# Digital_Output_Board.net
KiCad netlist of a schematic drawn in EAGLE
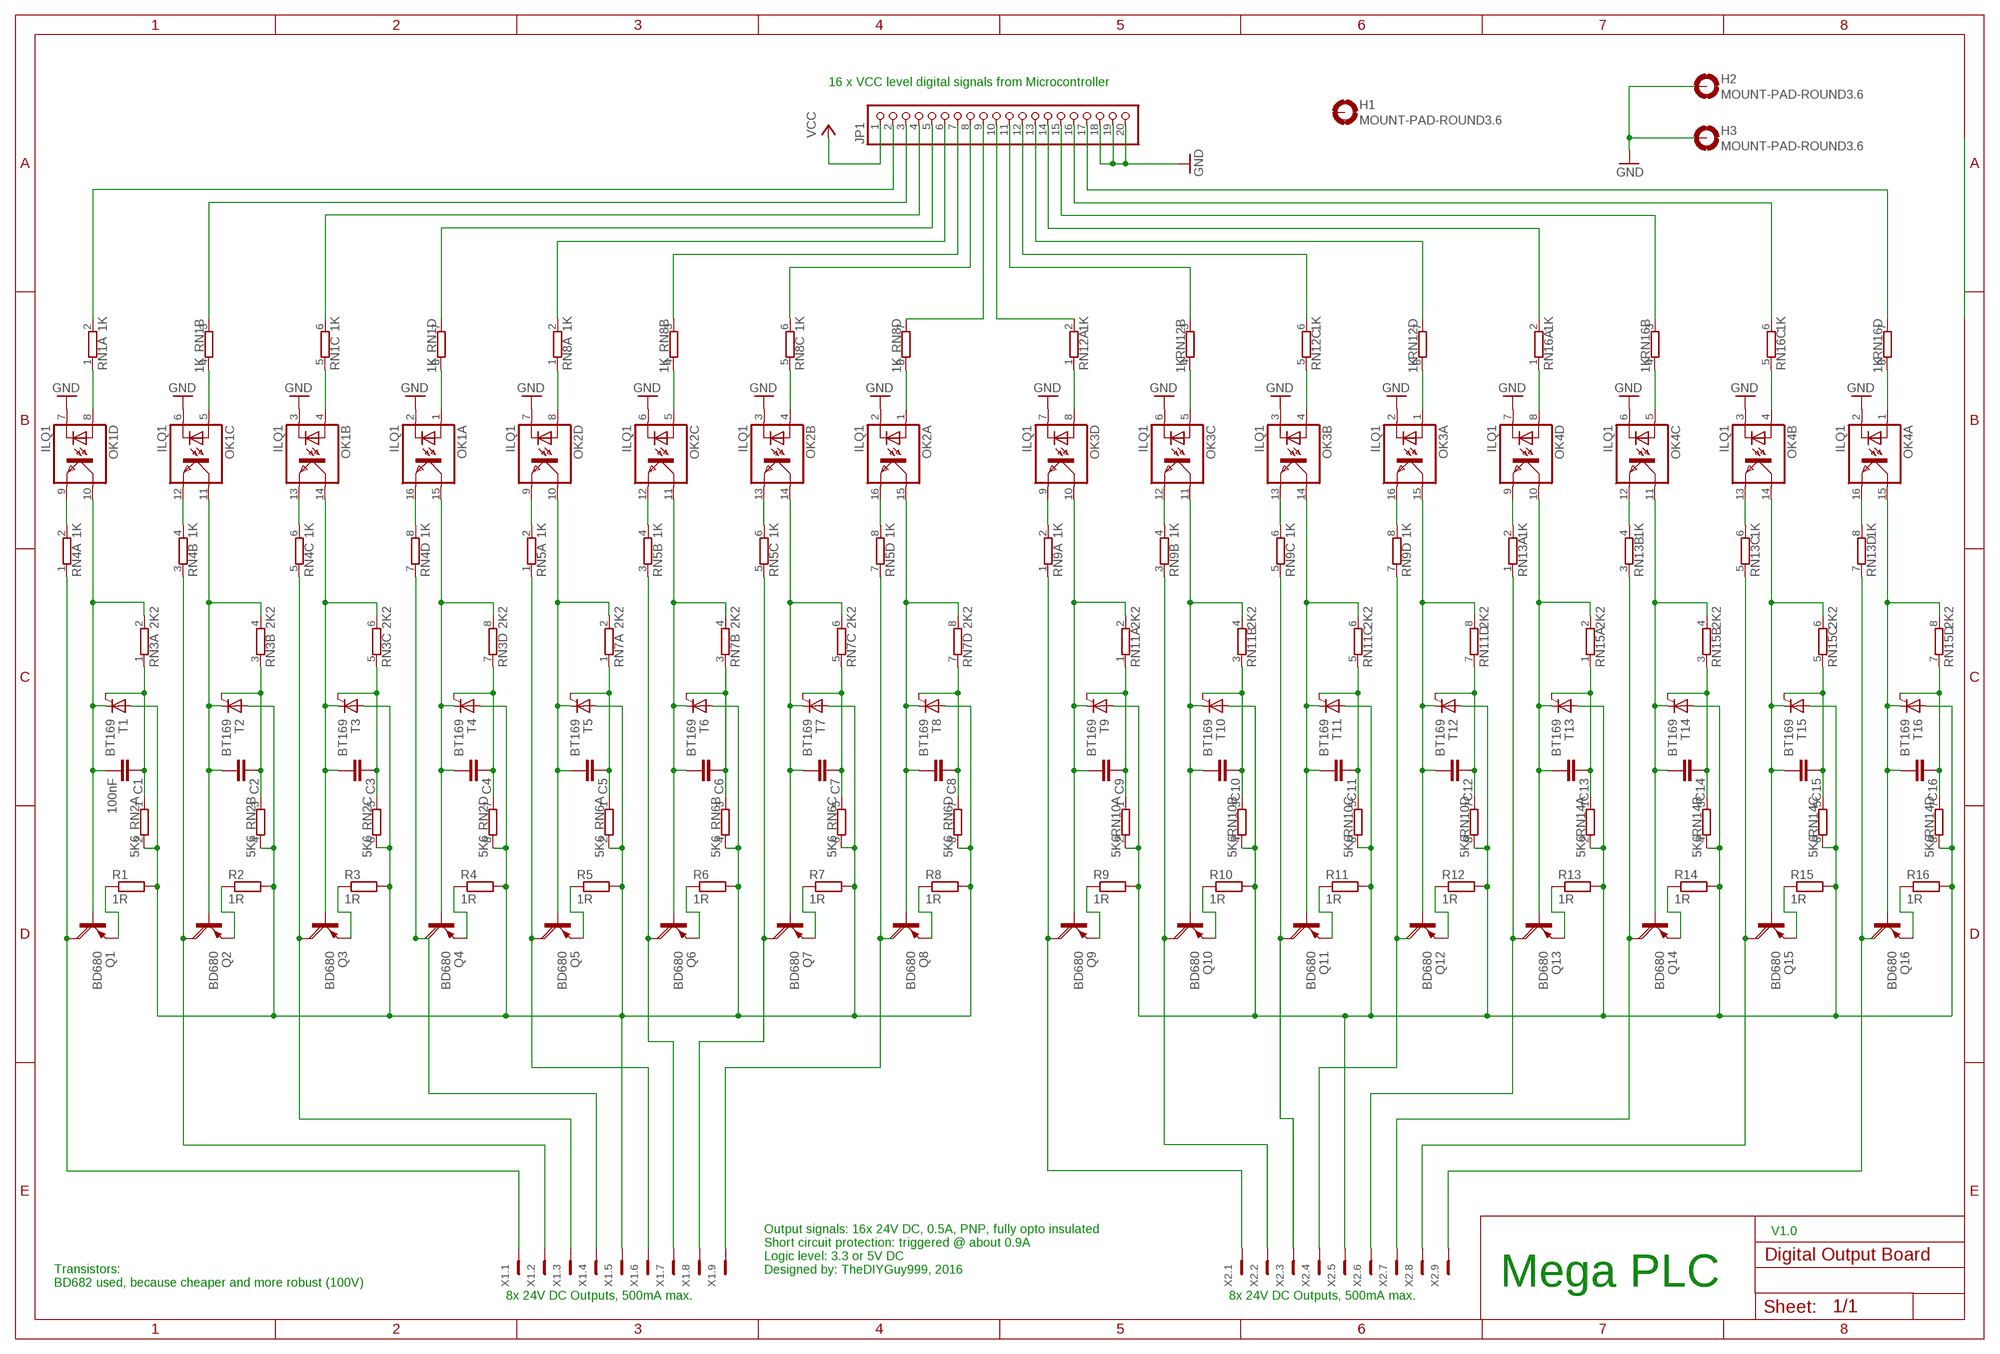
[diagram p0: schematic, sheet 1]

(export (version "E")
  (design (tool "Eeschema 10.0.6"))
  (components
    (comp (ref "C1")
      (value "100nF")
      (footprint "eagle-import:C025-024X044")
      (libsource (lib "eagle-import") (part "C-EU025-024X044"))
    )
    (comp (ref "C2")
      (value "C-EU025-024X044")
      (footprint "eagle-import:C025-024X044")
      (libsource (lib "eagle-import") (part "C-EU025-024X044"))
    )
    (comp (ref "C3")
      (value "C-EU025-024X044")
      (footprint "eagle-import:C025-024X044")
      (libsource (lib "eagle-import") (part "C-EU025-024X044"))
    )
    (comp (ref "C4")
      (value "C-EU025-024X044")
      (footprint "eagle-import:C025-024X044")
      (libsource (lib "eagle-import") (part "C-EU025-024X044"))
    )
    (comp (ref "C5")
      (value "C-EU025-024X044")
      (footprint "eagle-import:C025-024X044")
      (libsource (lib "eagle-import") (part "C-EU025-024X044"))
    )
    (comp (ref "C6")
      (value "C-EU025-024X044")
      (footprint "eagle-import:C025-024X044")
      (libsource (lib "eagle-import") (part "C-EU025-024X044"))
    )
    (comp (ref "C7")
      (value "C-EU025-024X044")
      (footprint "eagle-import:C025-024X044")
      (libsource (lib "eagle-import") (part "C-EU025-024X044"))
    )
    (comp (ref "C8")
      (value "C-EU025-024X044")
      (footprint "eagle-import:C025-024X044")
      (libsource (lib "eagle-import") (part "C-EU025-024X044"))
    )
    (comp (ref "C9")
      (value "C-EU025-024X044")
      (footprint "eagle-import:C025-024X044")
      (libsource (lib "eagle-import") (part "C-EU025-024X044"))
    )
    (comp (ref "C10")
      (value "C-EU025-024X044")
      (footprint "eagle-import:C025-024X044")
      (libsource (lib "eagle-import") (part "C-EU025-024X044"))
    )
    (comp (ref "C11")
      (value "C-EU025-024X044")
      (footprint "eagle-import:C025-024X044")
      (libsource (lib "eagle-import") (part "C-EU025-024X044"))
    )
    (comp (ref "C12")
      (value "C-EU025-024X044")
      (footprint "eagle-import:C025-024X044")
      (libsource (lib "eagle-import") (part "C-EU025-024X044"))
    )
    (comp (ref "C13")
      (value "C-EU025-024X044")
      (footprint "eagle-import:C025-024X044")
      (libsource (lib "eagle-import") (part "C-EU025-024X044"))
    )
    (comp (ref "C14")
      (value "C-EU025-024X044")
      (footprint "eagle-import:C025-024X044")
      (libsource (lib "eagle-import") (part "C-EU025-024X044"))
    )
    (comp (ref "C15")
      (value "C-EU025-024X044")
      (footprint "eagle-import:C025-024X044")
      (libsource (lib "eagle-import") (part "C-EU025-024X044"))
    )
    (comp (ref "C16")
      (value "C-EU025-024X044")
      (footprint "eagle-import:C025-024X044")
      (libsource (lib "eagle-import") (part "C-EU025-024X044"))
    )
    (comp (ref "H1")
      (value "MOUNT-PAD-ROUND3.6")
      (footprint "eagle-import:3,6-PAD")
      (libsource (lib "eagle-import") (part "MOUNT-PAD-ROUND3.6"))
    )
    (comp (ref "H2")
      (value "MOUNT-PAD-ROUND3.6")
      (footprint "eagle-import:3,6-PAD")
      (libsource (lib "eagle-import") (part "MOUNT-PAD-ROUND3.6"))
    )
    (comp (ref "H3")
      (value "MOUNT-PAD-ROUND3.6")
      (footprint "eagle-import:3,6-PAD")
      (libsource (lib "eagle-import") (part "MOUNT-PAD-ROUND3.6"))
    )
    (comp (ref "JP1")
      (value "PINHD-1X20/90")
      (footprint "eagle-import:1X20_90")
      (libsource (lib "eagle-import") (part "PINHD-1X20/90"))
    )
    (comp (ref "OK1")
      (value "ILQ1")
      (footprint "eagle-import:DIL16")
      (fields (field (name "MF") "VISHAY/TELEFUNKEN"))
      (libsource (lib "eagle-import") (part "ILQ1"))
    )
    (comp (ref "OK2")
      (value "ILQ1")
      (footprint "eagle-import:DIL16")
      (fields (field (name "MF") "VISHAY/TELEFUNKEN"))
      (libsource (lib "eagle-import") (part "ILQ1"))
    )
    (comp (ref "OK3")
      (value "ILQ1")
      (footprint "eagle-import:DIL16")
      (fields (field (name "MF") "VISHAY/TELEFUNKEN"))
      (libsource (lib "eagle-import") (part "ILQ1"))
    )
    (comp (ref "OK4")
      (value "ILQ1")
      (footprint "eagle-import:DIL16")
      (fields (field (name "MF") "VISHAY/TELEFUNKEN"))
      (libsource (lib "eagle-import") (part "ILQ1"))
    )
    (comp (ref "Q1")
      (value "BD680")
      (footprint "eagle-import:TO126AV")
      (libsource (lib "eagle-import") (part "BD680"))
    )
    (comp (ref "Q2")
      (value "BD680")
      (footprint "eagle-import:TO126AV")
      (libsource (lib "eagle-import") (part "BD680"))
    )
    (comp (ref "Q3")
      (value "BD680")
      (footprint "eagle-import:TO126AV")
      (libsource (lib "eagle-import") (part "BD680"))
    )
    (comp (ref "Q4")
      (value "BD680")
      (footprint "eagle-import:TO126AV")
      (libsource (lib "eagle-import") (part "BD680"))
    )
    (comp (ref "Q5")
      (value "BD680")
      (footprint "eagle-import:TO126AV")
      (libsource (lib "eagle-import") (part "BD680"))
    )
    (comp (ref "Q6")
      (value "BD680")
      (footprint "eagle-import:TO126AV")
      (libsource (lib "eagle-import") (part "BD680"))
    )
    (comp (ref "Q7")
      (value "BD680")
      (footprint "eagle-import:TO126AV")
      (libsource (lib "eagle-import") (part "BD680"))
    )
    (comp (ref "Q8")
      (value "BD680")
      (footprint "eagle-import:TO126AV")
      (libsource (lib "eagle-import") (part "BD680"))
    )
    (comp (ref "Q9")
      (value "BD680")
      (footprint "eagle-import:TO126AV")
      (libsource (lib "eagle-import") (part "BD680"))
    )
    (comp (ref "Q10")
      (value "BD680")
      (footprint "eagle-import:TO126AV")
      (libsource (lib "eagle-import") (part "BD680"))
    )
    (comp (ref "Q11")
      (value "BD680")
      (footprint "eagle-import:TO126AV")
      (libsource (lib "eagle-import") (part "BD680"))
    )
    (comp (ref "Q12")
      (value "BD680")
      (footprint "eagle-import:TO126AV")
      (libsource (lib "eagle-import") (part "BD680"))
    )
    (comp (ref "Q13")
      (value "BD680")
      (footprint "eagle-import:TO126AV")
      (libsource (lib "eagle-import") (part "BD680"))
    )
    (comp (ref "Q14")
      (value "BD680")
      (footprint "eagle-import:TO126AV")
      (libsource (lib "eagle-import") (part "BD680"))
    )
    (comp (ref "Q15")
      (value "BD680")
      (footprint "eagle-import:TO126AV")
      (libsource (lib "eagle-import") (part "BD680"))
    )
    (comp (ref "Q16")
      (value "BD680")
      (footprint "eagle-import:TO126AV")
      (libsource (lib "eagle-import") (part "BD680"))
    )
    (comp (ref "R1")
      (value "1R")
      (footprint "eagle-import:0207_10")
      (libsource (lib "eagle-import") (part "R-EU_0207/10"))
    )
    (comp (ref "R2")
      (value "1R")
      (footprint "eagle-import:0207_10")
      (libsource (lib "eagle-import") (part "R-EU_0207/10"))
    )
    (comp (ref "R3")
      (value "1R")
      (footprint "eagle-import:0207_10")
      (libsource (lib "eagle-import") (part "R-EU_0207/10"))
    )
    (comp (ref "R4")
      (value "1R")
      (footprint "eagle-import:0207_10")
      (libsource (lib "eagle-import") (part "R-EU_0207/10"))
    )
    (comp (ref "R5")
      (value "1R")
      (footprint "eagle-import:0207_10")
      (libsource (lib "eagle-import") (part "R-EU_0207/10"))
    )
    (comp (ref "R6")
      (value "1R")
      (footprint "eagle-import:0207_10")
      (libsource (lib "eagle-import") (part "R-EU_0207/10"))
    )
    (comp (ref "R7")
      (value "1R")
      (footprint "eagle-import:0207_10")
      (libsource (lib "eagle-import") (part "R-EU_0207/10"))
    )
    (comp (ref "R8")
      (value "1R")
      (footprint "eagle-import:0207_10")
      (libsource (lib "eagle-import") (part "R-EU_0207/10"))
    )
    (comp (ref "R9")
      (value "1R")
      (footprint "eagle-import:0207_10")
      (libsource (lib "eagle-import") (part "R-EU_0207/10"))
    )
    (comp (ref "R10")
      (value "1R")
      (footprint "eagle-import:0207_10")
      (libsource (lib "eagle-import") (part "R-EU_0207/10"))
    )
    (comp (ref "R11")
      (value "1R")
      (footprint "eagle-import:0207_10")
      (libsource (lib "eagle-import") (part "R-EU_0207/10"))
    )
    (comp (ref "R12")
      (value "1R")
      (footprint "eagle-import:0207_10")
      (libsource (lib "eagle-import") (part "R-EU_0207/10"))
    )
    (comp (ref "R13")
      (value "1R")
      (footprint "eagle-import:0207_10")
      (libsource (lib "eagle-import") (part "R-EU_0207/10"))
    )
    (comp (ref "R14")
      (value "1R")
      (footprint "eagle-import:0207_10")
      (libsource (lib "eagle-import") (part "R-EU_0207/10"))
    )
    (comp (ref "R15")
      (value "1R")
      (footprint "eagle-import:0207_10")
      (libsource (lib "eagle-import") (part "R-EU_0207/10"))
    )
    (comp (ref "R16")
      (value "1R")
      (footprint "eagle-import:0207_10")
      (libsource (lib "eagle-import") (part "R-EU_0207/10"))
    )
    (comp (ref "RN1")
      (value "1K")
      (footprint "eagle-import:SIL8")
      (libsource (lib "eagle-import") (part "E4R"))
    )
    (comp (ref "RN2")
      (value "5K6")
      (footprint "eagle-import:SIL8")
      (libsource (lib "eagle-import") (part "E4R"))
    )
    (comp (ref "RN3")
      (value "2K2")
      (footprint "eagle-import:SIL8")
      (libsource (lib "eagle-import") (part "E4R"))
    )
    (comp (ref "RN4")
      (value "1K")
      (footprint "eagle-import:SIL8")
      (libsource (lib "eagle-import") (part "E4R"))
    )
    (comp (ref "RN5")
      (value "1K")
      (footprint "eagle-import:SIL8")
      (libsource (lib "eagle-import") (part "E4R"))
    )
    (comp (ref "RN6")
      (value "5K6")
      (footprint "eagle-import:SIL8")
      (libsource (lib "eagle-import") (part "E4R"))
    )
    (comp (ref "RN7")
      (value "2K2")
      (footprint "eagle-import:SIL8")
      (libsource (lib "eagle-import") (part "E4R"))
    )
    (comp (ref "RN8")
      (value "1K")
      (footprint "eagle-import:SIL8")
      (libsource (lib "eagle-import") (part "E4R"))
    )
    (comp (ref "RN9")
      (value "1K")
      (footprint "eagle-import:SIL8")
      (libsource (lib "eagle-import") (part "E4R"))
    )
    (comp (ref "RN10")
      (value "5K6")
      (footprint "eagle-import:SIL8")
      (libsource (lib "eagle-import") (part "E4R"))
    )
    (comp (ref "RN11")
      (value "2K2")
      (footprint "eagle-import:SIL8")
      (libsource (lib "eagle-import") (part "E4R"))
    )
    (comp (ref "RN12")
      (value "1K")
      (footprint "eagle-import:SIL8")
      (libsource (lib "eagle-import") (part "E4R"))
    )
    (comp (ref "RN13")
      (value "1K")
      (footprint "eagle-import:SIL8")
      (libsource (lib "eagle-import") (part "E4R"))
    )
    (comp (ref "RN14")
      (value "5K6")
      (footprint "eagle-import:SIL8")
      (libsource (lib "eagle-import") (part "E4R"))
    )
    (comp (ref "RN15")
      (value "2K2")
      (footprint "eagle-import:SIL8")
      (libsource (lib "eagle-import") (part "E4R"))
    )
    (comp (ref "RN16")
      (value "1K")
      (footprint "eagle-import:SIL8")
      (libsource (lib "eagle-import") (part "E4R"))
    )
    (comp (ref "T1")
      (value "BT169")
      (footprint "eagle-import:TO92-2")
      (libsource (lib "eagle-import") (part "BT169"))
    )
    (comp (ref "T2")
      (value "BT169")
      (footprint "eagle-import:TO92-2")
      (libsource (lib "eagle-import") (part "BT169"))
    )
    (comp (ref "T3")
      (value "BT169")
      (footprint "eagle-import:TO92-2")
      (libsource (lib "eagle-import") (part "BT169"))
    )
    (comp (ref "T4")
      (value "BT169")
      (footprint "eagle-import:TO92-2")
      (libsource (lib "eagle-import") (part "BT169"))
    )
    (comp (ref "T5")
      (value "BT169")
      (footprint "eagle-import:TO92-2")
      (libsource (lib "eagle-import") (part "BT169"))
    )
    (comp (ref "T6")
      (value "BT169")
      (footprint "eagle-import:TO92-2")
      (libsource (lib "eagle-import") (part "BT169"))
    )
    (comp (ref "T7")
      (value "BT169")
      (footprint "eagle-import:TO92-2")
      (libsource (lib "eagle-import") (part "BT169"))
    )
    (comp (ref "T8")
      (value "BT169")
      (footprint "eagle-import:TO92-2")
      (libsource (lib "eagle-import") (part "BT169"))
    )
    (comp (ref "T9")
      (value "BT169")
      (footprint "eagle-import:TO92-2")
      (libsource (lib "eagle-import") (part "BT169"))
    )
    (comp (ref "T10")
      (value "BT169")
      (footprint "eagle-import:TO92-2")
      (libsource (lib "eagle-import") (part "BT169"))
    )
    (comp (ref "T11")
      (value "BT169")
      (footprint "eagle-import:TO92-2")
      (libsource (lib "eagle-import") (part "BT169"))
    )
    (comp (ref "T12")
      (value "BT169")
      (footprint "eagle-import:TO92-2")
      (libsource (lib "eagle-import") (part "BT169"))
    )
    (comp (ref "T13")
      (value "BT169")
      (footprint "eagle-import:TO92-2")
      (libsource (lib "eagle-import") (part "BT169"))
    )
    (comp (ref "T14")
      (value "BT169")
      (footprint "eagle-import:TO92-2")
      (libsource (lib "eagle-import") (part "BT169"))
    )
    (comp (ref "T15")
      (value "BT169")
      (footprint "eagle-import:TO92-2")
      (libsource (lib "eagle-import") (part "BT169"))
    )
    (comp (ref "T16")
      (value "BT169")
      (footprint "eagle-import:TO92-2")
      (libsource (lib "eagle-import") (part "BT169"))
    )
    (comp (ref "X1")
      (value "MC9")
      (footprint "eagle-import:MC9")
      (libsource (lib "eagle-import") (part "MC9"))
    )
    (comp (ref "X2")
      (value "MC9")
      (footprint "eagle-import:MC9")
      (libsource (lib "eagle-import") (part "MC9"))
    )
  )
  (nets
    (net (code "1") (name "GND") (class "Default")
      (node (ref "H2") (pin "B3,6") (pinfunction "MOUNT_B3,6") (pintype "passive"))
      (node (ref "H3") (pin "B3,6") (pinfunction "MOUNT_B3,6") (pintype "passive"))
      (node (ref "JP1") (pin "18") (pinfunction "18_18") (pintype "passive"))
      (node (ref "JP1") (pin "19") (pinfunction "19_19") (pintype "passive"))
      (node (ref "JP1") (pin "20") (pinfunction "20_20") (pintype "passive"))
      (node (ref "OK1") (pin "2") (pinfunction "C_2") (pintype "passive"))
      (node (ref "OK1") (pin "3") (pinfunction "C_3") (pintype "passive"))
      (node (ref "OK1") (pin "6") (pinfunction "C_6") (pintype "passive"))
      (node (ref "OK1") (pin "7") (pinfunction "C_7") (pintype "passive"))
      (node (ref "OK2") (pin "2") (pinfunction "C_2") (pintype "passive"))
      (node (ref "OK2") (pin "3") (pinfunction "C_3") (pintype "passive"))
      (node (ref "OK2") (pin "6") (pinfunction "C_6") (pintype "passive"))
      (node (ref "OK2") (pin "7") (pinfunction "C_7") (pintype "passive"))
      (node (ref "OK3") (pin "2") (pinfunction "C_2") (pintype "passive"))
      (node (ref "OK3") (pin "3") (pinfunction "C_3") (pintype "passive"))
      (node (ref "OK3") (pin "6") (pinfunction "C_6") (pintype "passive"))
      (node (ref "OK3") (pin "7") (pinfunction "C_7") (pintype "passive"))
      (node (ref "OK4") (pin "2") (pinfunction "C_2") (pintype "passive"))
      (node (ref "OK4") (pin "3") (pinfunction "C_3") (pintype "passive"))
      (node (ref "OK4") (pin "6") (pinfunction "C_6") (pintype "passive"))
      (node (ref "OK4") (pin "7") (pinfunction "C_7") (pintype "passive"))
    )
    (net (code "2") (name "Net-(C1-Pad1)") (class "Default")
      (node (ref "C1") (pin "1") (pinfunction "1_1") (pintype "passive"))
      (node (ref "RN2") (pin "1") (pinfunction "1_1") (pintype "passive"))
      (node (ref "RN3") (pin "1") (pinfunction "1_1") (pintype "passive"))
      (node (ref "T1") (pin "G") (pinfunction "G_G") (pintype "passive"))
    )
    (net (code "3") (name "Net-(C5-Pad1)") (class "Default")
      (node (ref "C5") (pin "1") (pinfunction "1_1") (pintype "passive"))
      (node (ref "RN6") (pin "1") (pinfunction "1_1") (pintype "passive"))
      (node (ref "RN7") (pin "1") (pinfunction "1_1") (pintype "passive"))
      (node (ref "T5") (pin "G") (pinfunction "G_G") (pintype "passive"))
    )
    (net (code "4") (name "Net-(C9-Pad1)") (class "Default")
      (node (ref "C9") (pin "1") (pinfunction "1_1") (pintype "passive"))
      (node (ref "RN10") (pin "1") (pinfunction "1_1") (pintype "passive"))
      (node (ref "RN11") (pin "1") (pinfunction "1_1") (pintype "passive"))
      (node (ref "T9") (pin "G") (pinfunction "G_G") (pintype "passive"))
    )
    (net (code "5") (name "Net-(C13-Pad1)") (class "Default")
      (node (ref "C13") (pin "1") (pinfunction "1_1") (pintype "passive"))
      (node (ref "RN14") (pin "1") (pinfunction "1_1") (pintype "passive"))
      (node (ref "RN15") (pin "1") (pinfunction "1_1") (pintype "passive"))
      (node (ref "T13") (pin "G") (pinfunction "G_G") (pintype "passive"))
    )
    (net (code "6") (name "Net-(JP1-Pad2)") (class "Default")
      (node (ref "JP1") (pin "2") (pinfunction "2_2") (pintype "passive"))
      (node (ref "RN1") (pin "2") (pinfunction "2_2") (pintype "passive"))
    )
    (net (code "7") (name "Net-(JP1-Pad6)") (class "Default")
      (node (ref "JP1") (pin "6") (pinfunction "6_6") (pintype "passive"))
      (node (ref "RN8") (pin "2") (pinfunction "2_2") (pintype "passive"))
    )
    (net (code "8") (name "Net-(JP1-Pad10)") (class "Default")
      (node (ref "JP1") (pin "10") (pinfunction "10_10") (pintype "passive"))
      (node (ref "RN12") (pin "2") (pinfunction "2_2") (pintype "passive"))
    )
    (net (code "9") (name "Net-(JP1-Pad14)") (class "Default")
      (node (ref "JP1") (pin "14") (pinfunction "14_14") (pintype "passive"))
      (node (ref "RN16") (pin "2") (pinfunction "2_2") (pintype "passive"))
    )
    (net (code "10") (name "Net-(OK1A-A)") (class "Default")
      (node (ref "OK1") (pin "1") (pinfunction "A_1") (pintype "passive"))
      (node (ref "RN1") (pin "8") (pinfunction "2_8") (pintype "passive"))
    )
    (net (code "11") (name "Net-(OK1A-COL)") (class "Default")
      (node (ref "C4") (pin "2") (pinfunction "2_2") (pintype "passive"))
      (node (ref "OK1") (pin "15") (pinfunction "COL_15") (pintype "passive"))
      (node (ref "Q4") (pin "B") (pinfunction "B_B") (pintype "passive"))
      (node (ref "RN3") (pin "8") (pinfunction "2_8") (pintype "passive"))
      (node (ref "T4") (pin "C") (pinfunction "C_C") (pintype "passive"))
    )
    (net (code "12") (name "Net-(OK1A-EMIT)") (class "Default")
      (node (ref "OK1") (pin "16") (pinfunction "EMIT_16") (pintype "passive"))
      (node (ref "RN4") (pin "8") (pinfunction "2_8") (pintype "passive"))
    )
    (net (code "13") (name "Net-(OK1B-A)") (class "Default")
      (node (ref "OK1") (pin "4") (pinfunction "A_4") (pintype "passive"))
      (node (ref "RN1") (pin "5") (pinfunction "1_5") (pintype "passive"))
    )
    (net (code "14") (name "Net-(OK1B-COL)") (class "Default")
      (node (ref "C3") (pin "2") (pinfunction "2_2") (pintype "passive"))
      (node (ref "OK1") (pin "14") (pinfunction "COL_14") (pintype "passive"))
      (node (ref "Q3") (pin "B") (pinfunction "B_B") (pintype "passive"))
      (node (ref "RN3") (pin "6") (pinfunction "2_6") (pintype "passive"))
      (node (ref "T3") (pin "C") (pinfunction "C_C") (pintype "passive"))
    )
    (net (code "15") (name "Net-(OK1B-EMIT)") (class "Default")
      (node (ref "OK1") (pin "13") (pinfunction "EMIT_13") (pintype "passive"))
      (node (ref "RN4") (pin "6") (pinfunction "2_6") (pintype "passive"))
    )
    (net (code "16") (name "Net-(OK1C-A)") (class "Default")
      (node (ref "OK1") (pin "5") (pinfunction "A_5") (pintype "passive"))
      (node (ref "RN1") (pin "4") (pinfunction "2_4") (pintype "passive"))
    )
    (net (code "17") (name "Net-(OK1C-COL)") (class "Default")
      (node (ref "C2") (pin "2") (pinfunction "2_2") (pintype "passive"))
      (node (ref "OK1") (pin "11") (pinfunction "COL_11") (pintype "passive"))
      (node (ref "Q2") (pin "B") (pinfunction "B_B") (pintype "passive"))
      (node (ref "RN3") (pin "4") (pinfunction "2_4") (pintype "passive"))
      (node (ref "T2") (pin "C") (pinfunction "C_C") (pintype "passive"))
    )
    (net (code "18") (name "Net-(OK1C-EMIT)") (class "Default")
      (node (ref "OK1") (pin "12") (pinfunction "EMIT_12") (pintype "passive"))
      (node (ref "RN4") (pin "4") (pinfunction "2_4") (pintype "passive"))
    )
    (net (code "19") (name "Net-(OK1D-A)") (class "Default")
      (node (ref "OK1") (pin "8") (pinfunction "A_8") (pintype "passive"))
      (node (ref "RN1") (pin "1") (pinfunction "1_1") (pintype "passive"))
    )
    (net (code "20") (name "Net-(OK1D-COL)") (class "Default")
      (node (ref "C1") (pin "2") (pinfunction "2_2") (pintype "passive"))
      (node (ref "OK1") (pin "10") (pinfunction "COL_10") (pintype "passive"))
      (node (ref "Q1") (pin "B") (pinfunction "B_B") (pintype "passive"))
      (node (ref "RN3") (pin "2") (pinfunction "2_2") (pintype "passive"))
      (node (ref "T1") (pin "C") (pinfunction "C_C") (pintype "passive"))
    )
    (net (code "21") (name "Net-(OK1D-EMIT)") (class "Default")
      (node (ref "OK1") (pin "9") (pinfunction "EMIT_9") (pintype "passive"))
      (node (ref "RN4") (pin "2") (pinfunction "2_2") (pintype "passive"))
    )
    (net (code "22") (name "Net-(OK2A-A)") (class "Default")
      (node (ref "OK2") (pin "1") (pinfunction "A_1") (pintype "passive"))
      (node (ref "RN8") (pin "8") (pinfunction "2_8") (pintype "passive"))
    )
    (net (code "23") (name "Net-(OK2A-COL)") (class "Default")
      (node (ref "C8") (pin "2") (pinfunction "2_2") (pintype "passive"))
      (node (ref "OK2") (pin "15") (pinfunction "COL_15") (pintype "passive"))
      (node (ref "Q8") (pin "B") (pinfunction "B_B") (pintype "passive"))
      (node (ref "RN7") (pin "8") (pinfunction "2_8") (pintype "passive"))
      (node (ref "T8") (pin "C") (pinfunction "C_C") (pintype "passive"))
    )
    (net (code "24") (name "Net-(OK2A-EMIT)") (class "Default")
      (node (ref "OK2") (pin "16") (pinfunction "EMIT_16") (pintype "passive"))
      (node (ref "RN5") (pin "8") (pinfunction "2_8") (pintype "passive"))
    )
    (net (code "25") (name "Net-(OK2B-A)") (class "Default")
      (node (ref "OK2") (pin "4") (pinfunction "A_4") (pintype "passive"))
      (node (ref "RN8") (pin "5") (pinfunction "1_5") (pintype "passive"))
    )
    (net (code "26") (name "Net-(OK2B-COL)") (class "Default")
      (node (ref "C7") (pin "2") (pinfunction "2_2") (pintype "passive"))
      (node (ref "OK2") (pin "14") (pinfunction "COL_14") (pintype "passive"))
      (node (ref "Q7") (pin "B") (pinfunction "B_B") (pintype "passive"))
      (node (ref "RN7") (pin "6") (pinfunction "2_6") (pintype "passive"))
      (node (ref "T7") (pin "C") (pinfunction "C_C") (pintype "passive"))
    )
    (net (code "27") (name "Net-(OK2B-EMIT)") (class "Default")
      (node (ref "OK2") (pin "13") (pinfunction "EMIT_13") (pintype "passive"))
      (node (ref "RN5") (pin "6") (pinfunction "2_6") (pintype "passive"))
    )
    (net (code "28") (name "Net-(OK2C-A)") (class "Default")
      (node (ref "OK2") (pin "5") (pinfunction "A_5") (pintype "passive"))
      (node (ref "RN8") (pin "4") (pinfunction "2_4") (pintype "passive"))
    )
    (net (code "29") (name "Net-(OK2C-COL)") (class "Default")
      (node (ref "C6") (pin "2") (pinfunction "2_2") (pintype "passive"))
      (node (ref "OK2") (pin "11") (pinfunction "COL_11") (pintype "passive"))
      (node (ref "Q6") (pin "B") (pinfunction "B_B") (pintype "passive"))
      (node (ref "RN7") (pin "4") (pinfunction "2_4") (pintype "passive"))
      (node (ref "T6") (pin "C") (pinfunction "C_C") (pintype "passive"))
    )
    (net (code "30") (name "Net-(OK2C-EMIT)") (class "Default")
      (node (ref "OK2") (pin "12") (pinfunction "EMIT_12") (pintype "passive"))
      (node (ref "RN5") (pin "4") (pinfunction "2_4") (pintype "passive"))
    )
    (net (code "31") (name "Net-(OK2D-A)") (class "Default")
      (node (ref "OK2") (pin "8") (pinfunction "A_8") (pintype "passive"))
      (node (ref "RN8") (pin "1") (pinfunction "1_1") (pintype "passive"))
    )
    (net (code "32") (name "Net-(OK2D-COL)") (class "Default")
      (node (ref "C5") (pin "2") (pinfunction "2_2") (pintype "passive"))
      (node (ref "OK2") (pin "10") (pinfunction "COL_10") (pintype "passive"))
      (node (ref "Q5") (pin "B") (pinfunction "B_B") (pintype "passive"))
      (node (ref "RN7") (pin "2") (pinfunction "2_2") (pintype "passive"))
      (node (ref "T5") (pin "C") (pinfunction "C_C") (pintype "passive"))
    )
    (net (code "33") (name "Net-(OK2D-EMIT)") (class "Default")
      (node (ref "OK2") (pin "9") (pinfunction "EMIT_9") (pintype "passive"))
      (node (ref "RN5") (pin "2") (pinfunction "2_2") (pintype "passive"))
    )
    (net (code "34") (name "Net-(OK3A-A)") (class "Default")
      (node (ref "OK3") (pin "1") (pinfunction "A_1") (pintype "passive"))
      (node (ref "RN12") (pin "8") (pinfunction "2_8") (pintype "passive"))
    )
    (net (code "35") (name "Net-(OK3A-COL)") (class "Default")
      (node (ref "C12") (pin "2") (pinfunction "2_2") (pintype "passive"))
      (node (ref "OK3") (pin "15") (pinfunction "COL_15") (pintype "passive"))
      (node (ref "Q12") (pin "B") (pinfunction "B_B") (pintype "passive"))
      (node (ref "RN11") (pin "8") (pinfunction "2_8") (pintype "passive"))
      (node (ref "T12") (pin "C") (pinfunction "C_C") (pintype "passive"))
    )
    (net (code "36") (name "Net-(OK3A-EMIT)") (class "Default")
      (node (ref "OK3") (pin "16") (pinfunction "EMIT_16") (pintype "passive"))
      (node (ref "RN9") (pin "8") (pinfunction "2_8") (pintype "passive"))
    )
    (net (code "37") (name "Net-(OK3B-A)") (class "Default")
      (node (ref "OK3") (pin "4") (pinfunction "A_4") (pintype "passive"))
      (node (ref "RN12") (pin "5") (pinfunction "1_5") (pintype "passive"))
    )
    (net (code "38") (name "Net-(OK3B-COL)") (class "Default")
      (node (ref "C11") (pin "2") (pinfunction "2_2") (pintype "passive"))
      (node (ref "OK3") (pin "14") (pinfunction "COL_14") (pintype "passive"))
      (node (ref "Q11") (pin "B") (pinfunction "B_B") (pintype "passive"))
      (node (ref "RN11") (pin "6") (pinfunction "2_6") (pintype "passive"))
      (node (ref "T11") (pin "C") (pinfunction "C_C") (pintype "passive"))
    )
    (net (code "39") (name "Net-(OK3B-EMIT)") (class "Default")
      (node (ref "OK3") (pin "13") (pinfunction "EMIT_13") (pintype "passive"))
      (node (ref "RN9") (pin "6") (pinfunction "2_6") (pintype "passive"))
    )
    (net (code "40") (name "Net-(OK3C-A)") (class "Default")
      (node (ref "OK3") (pin "5") (pinfunction "A_5") (pintype "passive"))
      (node (ref "RN12") (pin "4") (pinfunction "2_4") (pintype "passive"))
    )
    (net (code "41") (name "Net-(OK3C-COL)") (class "Default")
      (node (ref "C10") (pin "2") (pinfunction "2_2") (pintype "passive"))
      (node (ref "OK3") (pin "11") (pinfunction "COL_11") (pintype "passive"))
      (node (ref "Q10") (pin "B") (pinfunction "B_B") (pintype "passive"))
      (node (ref "RN11") (pin "4") (pinfunction "2_4") (pintype "passive"))
      (node (ref "T10") (pin "C") (pinfunction "C_C") (pintype "passive"))
    )
    (net (code "42") (name "Net-(OK3C-EMIT)") (class "Default")
      (node (ref "OK3") (pin "12") (pinfunction "EMIT_12") (pintype "passive"))
      (node (ref "RN9") (pin "4") (pinfunction "2_4") (pintype "passive"))
    )
    (net (code "43") (name "Net-(OK3D-A)") (class "Default")
      (node (ref "OK3") (pin "8") (pinfunction "A_8") (pintype "passive"))
      (node (ref "RN12") (pin "1") (pinfunction "1_1") (pintype "passive"))
    )
    (net (code "44") (name "Net-(OK3D-COL)") (class "Default")
      (node (ref "C9") (pin "2") (pinfunction "2_2") (pintype "passive"))
      (node (ref "OK3") (pin "10") (pinfunction "COL_10") (pintype "passive"))
      (node (ref "Q9") (pin "B") (pinfunction "B_B") (pintype "passive"))
      (node (ref "RN11") (pin "2") (pinfunction "2_2") (pintype "passive"))
      (node (ref "T9") (pin "C") (pinfunction "C_C") (pintype "passive"))
    )
    (net (code "45") (name "Net-(OK3D-EMIT)") (class "Default")
      (node (ref "OK3") (pin "9") (pinfunction "EMIT_9") (pintype "passive"))
      (node (ref "RN9") (pin "2") (pinfunction "2_2") (pintype "passive"))
    )
    (net (code "46") (name "Net-(OK4A-A)") (class "Default")
      (node (ref "OK4") (pin "1") (pinfunction "A_1") (pintype "passive"))
      (node (ref "RN16") (pin "8") (pinfunction "2_8") (pintype "passive"))
    )
    (net (code "47") (name "Net-(OK4A-COL)") (class "Default")
      (node (ref "C16") (pin "2") (pinfunction "2_2") (pintype "passive"))
      (node (ref "OK4") (pin "15") (pinfunction "COL_15") (pintype "passive"))
      (node (ref "Q16") (pin "B") (pinfunction "B_B") (pintype "passive"))
      (node (ref "RN15") (pin "8") (pinfunction "2_8") (pintype "passive"))
      (node (ref "T16") (pin "C") (pinfunction "C_C") (pintype "passive"))
    )
    (net (code "48") (name "Net-(OK4A-EMIT)") (class "Default")
      (node (ref "OK4") (pin "16") (pinfunction "EMIT_16") (pintype "passive"))
      (node (ref "RN13") (pin "8") (pinfunction "2_8") (pintype "passive"))
    )
    (net (code "49") (name "Net-(OK4B-A)") (class "Default")
      (node (ref "OK4") (pin "4") (pinfunction "A_4") (pintype "passive"))
      (node (ref "RN16") (pin "5") (pinfunction "1_5") (pintype "passive"))
    )
    (net (code "50") (name "Net-(OK4B-COL)") (class "Default")
      (node (ref "C15") (pin "2") (pinfunction "2_2") (pintype "passive"))
      (node (ref "OK4") (pin "14") (pinfunction "COL_14") (pintype "passive"))
      (node (ref "Q15") (pin "B") (pinfunction "B_B") (pintype "passive"))
      (node (ref "RN15") (pin "6") (pinfunction "2_6") (pintype "passive"))
      (node (ref "T15") (pin "C") (pinfunction "C_C") (pintype "passive"))
    )
    (net (code "51") (name "Net-(OK4B-EMIT)") (class "Default")
      (node (ref "OK4") (pin "13") (pinfunction "EMIT_13") (pintype "passive"))
      (node (ref "RN13") (pin "6") (pinfunction "2_6") (pintype "passive"))
    )
    (net (code "52") (name "Net-(OK4C-A)") (class "Default")
      (node (ref "OK4") (pin "5") (pinfunction "A_5") (pintype "passive"))
      (node (ref "RN16") (pin "4") (pinfunction "2_4") (pintype "passive"))
    )
    (net (code "53") (name "Net-(OK4C-COL)") (class "Default")
      (node (ref "C14") (pin "2") (pinfunction "2_2") (pintype "passive"))
      (node (ref "OK4") (pin "11") (pinfunction "COL_11") (pintype "passive"))
      (node (ref "Q14") (pin "B") (pinfunction "B_B") (pintype "passive"))
      (node (ref "RN15") (pin "4") (pinfunction "2_4") (pintype "passive"))
      (node (ref "T14") (pin "C") (pinfunction "C_C") (pintype "passive"))
    )
    (net (code "54") (name "Net-(OK4C-EMIT)") (class "Default")
      (node (ref "OK4") (pin "12") (pinfunction "EMIT_12") (pintype "passive"))
      (node (ref "RN13") (pin "4") (pinfunction "2_4") (pintype "passive"))
    )
    (net (code "55") (name "Net-(OK4D-A)") (class "Default")
      (node (ref "OK4") (pin "8") (pinfunction "A_8") (pintype "passive"))
      (node (ref "RN16") (pin "1") (pinfunction "1_1") (pintype "passive"))
    )
    (net (code "56") (name "Net-(OK4D-COL)") (class "Default")
      (node (ref "C13") (pin "2") (pinfunction "2_2") (pintype "passive"))
      (node (ref "OK4") (pin "10") (pinfunction "COL_10") (pintype "passive"))
      (node (ref "Q13") (pin "B") (pinfunction "B_B") (pintype "passive"))
      (node (ref "RN15") (pin "2") (pinfunction "2_2") (pintype "passive"))
      (node (ref "T13") (pin "C") (pinfunction "C_C") (pintype "passive"))
    )
    (net (code "57") (name "Net-(OK4D-EMIT)") (class "Default")
      (node (ref "OK4") (pin "9") (pinfunction "EMIT_9") (pintype "passive"))
      (node (ref "RN13") (pin "2") (pinfunction "2_2") (pintype "passive"))
    )
    (net (code "58") (name "Net-(Q1-PadE)") (class "Default")
      (node (ref "Q1") (pin "E") (pinfunction "E_E") (pintype "passive"))
      (node (ref "R1") (pin "1") (pinfunction "1_1") (pintype "passive"))
    )
    (net (code "59") (name "Net-(Q2-PadE)") (class "Default")
      (node (ref "Q2") (pin "E") (pinfunction "E_E") (pintype "passive"))
      (node (ref "R2") (pin "1") (pinfunction "1_1") (pintype "passive"))
    )
    (net (code "60") (name "Net-(Q3-PadE)") (class "Default")
      (node (ref "Q3") (pin "E") (pinfunction "E_E") (pintype "passive"))
      (node (ref "R3") (pin "1") (pinfunction "1_1") (pintype "passive"))
    )
    (net (code "61") (name "Net-(Q4-PadE)") (class "Default")
      (node (ref "Q4") (pin "E") (pinfunction "E_E") (pintype "passive"))
      (node (ref "R4") (pin "1") (pinfunction "1_1") (pintype "passive"))
    )
    (net (code "62") (name "Net-(Q5-PadE)") (class "Default")
      (node (ref "Q5") (pin "E") (pinfunction "E_E") (pintype "passive"))
      (node (ref "R5") (pin "1") (pinfunction "1_1") (pintype "passive"))
    )
    (net (code "63") (name "Net-(Q6-PadE)") (class "Default")
      (node (ref "Q6") (pin "E") (pinfunction "E_E") (pintype "passive"))
      (node (ref "R6") (pin "1") (pinfunction "1_1") (pintype "passive"))
    )
    (net (code "64") (name "Net-(Q7-PadE)") (class "Default")
      (node (ref "Q7") (pin "E") (pinfunction "E_E") (pintype "passive"))
      (node (ref "R7") (pin "1") (pinfunction "1_1") (pintype "passive"))
    )
    (net (code "65") (name "Net-(Q8-PadE)") (class "Default")
      (node (ref "Q8") (pin "E") (pinfunction "E_E") (pintype "passive"))
      (node (ref "R8") (pin "1") (pinfunction "1_1") (pintype "passive"))
    )
    (net (code "66") (name "Net-(Q9-PadE)") (class "Default")
      (node (ref "Q9") (pin "E") (pinfunction "E_E") (pintype "passive"))
      (node (ref "R9") (pin "1") (pinfunction "1_1") (pintype "passive"))
    )
    (net (code "67") (name "Net-(Q10-PadE)") (class "Default")
      (node (ref "Q10") (pin "E") (pinfunction "E_E") (pintype "passive"))
      (node (ref "R10") (pin "1") (pinfunction "1_1") (pintype "passive"))
    )
    (net (code "68") (name "Net-(Q11-PadE)") (class "Default")
      (node (ref "Q11") (pin "E") (pinfunction "E_E") (pintype "passive"))
      (node (ref "R11") (pin "1") (pinfunction "1_1") (pintype "passive"))
    )
    (net (code "69") (name "Net-(Q12-PadE)") (class "Default")
      (node (ref "Q12") (pin "E") (pinfunction "E_E") (pintype "passive"))
      (node (ref "R12") (pin "1") (pinfunction "1_1") (pintype "passive"))
    )
    (net (code "70") (name "Net-(Q13-PadE)") (class "Default")
      (node (ref "Q13") (pin "E") (pinfunction "E_E") (pintype "passive"))
      (node (ref "R13") (pin "1") (pinfunction "1_1") (pintype "passive"))
    )
    (net (code "71") (name "Net-(Q14-PadE)") (class "Default")
      (node (ref "Q14") (pin "E") (pinfunction "E_E") (pintype "passive"))
      (node (ref "R14") (pin "1") (pinfunction "1_1") (pintype "passive"))
    )
    (net (code "72") (name "Net-(Q15-PadE)") (class "Default")
      (node (ref "Q15") (pin "E") (pinfunction "E_E") (pintype "passive"))
      (node (ref "R15") (pin "1") (pinfunction "1_1") (pintype "passive"))
    )
    (net (code "73") (name "Net-(Q16-PadE)") (class "Default")
      (node (ref "Q16") (pin "E") (pinfunction "E_E") (pintype "passive"))
      (node (ref "R16") (pin "1") (pinfunction "1_1") (pintype "passive"))
    )
    (net (code "74") (name "Net-(RN1B-1)") (class "Default")
      (node (ref "JP1") (pin "3") (pinfunction "3_3") (pintype "passive"))
      (node (ref "RN1") (pin "3") (pinfunction "1_3") (pintype "passive"))
    )
    (net (code "75") (name "Net-(RN1C-2)") (class "Default")
      (node (ref "JP1") (pin "4") (pinfunction "4_4") (pintype "passive"))
      (node (ref "RN1") (pin "6") (pinfunction "2_6") (pintype "passive"))
    )
    (net (code "76") (name "Net-(RN1D-1)") (class "Default")
      (node (ref "JP1") (pin "5") (pinfunction "5_5") (pintype "passive"))
      (node (ref "RN1") (pin "7") (pinfunction "1_7") (pintype "passive"))
    )
    (net (code "77") (name "Net-(RN2B-1)") (class "Default")
      (node (ref "C2") (pin "1") (pinfunction "1_1") (pintype "passive"))
      (node (ref "RN2") (pin "3") (pinfunction "1_3") (pintype "passive"))
      (node (ref "RN3") (pin "3") (pinfunction "1_3") (pintype "passive"))
      (node (ref "T2") (pin "G") (pinfunction "G_G") (pintype "passive"))
    )
    (net (code "78") (name "Net-(RN2B-2)") (class "Default")
      (node (ref "R1") (pin "2") (pinfunction "2_2") (pintype "passive"))
      (node (ref "R2") (pin "2") (pinfunction "2_2") (pintype "passive"))
      (node (ref "R3") (pin "2") (pinfunction "2_2") (pintype "passive"))
      (node (ref "R4") (pin "2") (pinfunction "2_2") (pintype "passive"))
      (node (ref "R5") (pin "2") (pinfunction "2_2") (pintype "passive"))
      (node (ref "R6") (pin "2") (pinfunction "2_2") (pintype "passive"))
      (node (ref "R7") (pin "2") (pinfunction "2_2") (pintype "passive"))
      (node (ref "R8") (pin "2") (pinfunction "2_2") (pintype "passive"))
      (node (ref "RN2") (pin "2") (pinfunction "2_2") (pintype "passive"))
      (node (ref "RN2") (pin "4") (pinfunction "2_4") (pintype "passive"))
      (node (ref "RN2") (pin "6") (pinfunction "2_6") (pintype "passive"))
      (node (ref "RN2") (pin "8") (pinfunction "2_8") (pintype "passive"))
      (node (ref "RN6") (pin "2") (pinfunction "2_2") (pintype "passive"))
      (node (ref "RN6") (pin "4") (pinfunction "2_4") (pintype "passive"))
      (node (ref "RN6") (pin "6") (pinfunction "2_6") (pintype "passive"))
      (node (ref "RN6") (pin "8") (pinfunction "2_8") (pintype "passive"))
      (node (ref "T1") (pin "A") (pinfunction "A_A") (pintype "passive"))
      (node (ref "T2") (pin "A") (pinfunction "A_A") (pintype "passive"))
      (node (ref "T3") (pin "A") (pinfunction "A_A") (pintype "passive"))
      (node (ref "T4") (pin "A") (pinfunction "A_A") (pintype "passive"))
      (node (ref "T5") (pin "A") (pinfunction "A_A") (pintype "passive"))
      (node (ref "T6") (pin "A") (pinfunction "A_A") (pintype "passive"))
      (node (ref "T7") (pin "A") (pinfunction "A_A") (pintype "passive"))
      (node (ref "T8") (pin "A") (pinfunction "A_A") (pintype "passive"))
      (node (ref "X1") (pin "5") (pinfunction "SK_5") (pintype "passive"))
    )
    (net (code "79") (name "Net-(RN2C-1)") (class "Default")
      (node (ref "C3") (pin "1") (pinfunction "1_1") (pintype "passive"))
      (node (ref "RN2") (pin "5") (pinfunction "1_5") (pintype "passive"))
      (node (ref "RN3") (pin "5") (pinfunction "1_5") (pintype "passive"))
      (node (ref "T3") (pin "G") (pinfunction "G_G") (pintype "passive"))
    )
    (net (code "80") (name "Net-(RN2D-1)") (class "Default")
      (node (ref "C4") (pin "1") (pinfunction "1_1") (pintype "passive"))
      (node (ref "RN2") (pin "7") (pinfunction "1_7") (pintype "passive"))
      (node (ref "RN3") (pin "7") (pinfunction "1_7") (pintype "passive"))
      (node (ref "T4") (pin "G") (pinfunction "G_G") (pintype "passive"))
    )
    (net (code "81") (name "Net-(RN4B-1)") (class "Default")
      (node (ref "Q2") (pin "C") (pinfunction "C_C") (pintype "passive"))
      (node (ref "RN4") (pin "3") (pinfunction "1_3") (pintype "passive"))
      (node (ref "X1") (pin "2") (pinfunction "SK_2") (pintype "passive"))
    )
    (net (code "82") (name "Net-(RN4C-1)") (class "Default")
      (node (ref "Q3") (pin "C") (pinfunction "C_C") (pintype "passive"))
      (node (ref "RN4") (pin "5") (pinfunction "1_5") (pintype "passive"))
      (node (ref "X1") (pin "3") (pinfunction "SK_3") (pintype "passive"))
    )
    (net (code "83") (name "Net-(RN4D-1)") (class "Default")
      (node (ref "Q4") (pin "C") (pinfunction "C_C") (pintype "passive"))
      (node (ref "RN4") (pin "7") (pinfunction "1_7") (pintype "passive"))
      (node (ref "X1") (pin "4") (pinfunction "SK_4") (pintype "passive"))
    )
    (net (code "84") (name "Net-(RN5B-1)") (class "Default")
      (node (ref "Q6") (pin "C") (pinfunction "C_C") (pintype "passive"))
      (node (ref "RN5") (pin "3") (pinfunction "1_3") (pintype "passive"))
      (node (ref "X1") (pin "7") (pinfunction "SK_7") (pintype "passive"))
    )
    (net (code "85") (name "Net-(RN5C-1)") (class "Default")
      (node (ref "Q7") (pin "C") (pinfunction "C_C") (pintype "passive"))
      (node (ref "RN5") (pin "5") (pinfunction "1_5") (pintype "passive"))
      (node (ref "X1") (pin "8") (pinfunction "SK_8") (pintype "passive"))
    )
    (net (code "86") (name "Net-(RN5D-1)") (class "Default")
      (node (ref "Q8") (pin "C") (pinfunction "C_C") (pintype "passive"))
      (node (ref "RN5") (pin "7") (pinfunction "1_7") (pintype "passive"))
      (node (ref "X1") (pin "9") (pinfunction "SK_9") (pintype "passive"))
    )
    (net (code "87") (name "Net-(RN6B-1)") (class "Default")
      (node (ref "C6") (pin "1") (pinfunction "1_1") (pintype "passive"))
      (node (ref "RN6") (pin "3") (pinfunction "1_3") (pintype "passive"))
      (node (ref "RN7") (pin "3") (pinfunction "1_3") (pintype "passive"))
      (node (ref "T6") (pin "G") (pinfunction "G_G") (pintype "passive"))
    )
    (net (code "88") (name "Net-(RN6C-1)") (class "Default")
      (node (ref "C7") (pin "1") (pinfunction "1_1") (pintype "passive"))
      (node (ref "RN6") (pin "5") (pinfunction "1_5") (pintype "passive"))
      (node (ref "RN7") (pin "5") (pinfunction "1_5") (pintype "passive"))
      (node (ref "T7") (pin "G") (pinfunction "G_G") (pintype "passive"))
    )
    (net (code "89") (name "Net-(RN6D-1)") (class "Default")
      (node (ref "C8") (pin "1") (pinfunction "1_1") (pintype "passive"))
      (node (ref "RN6") (pin "7") (pinfunction "1_7") (pintype "passive"))
      (node (ref "RN7") (pin "7") (pinfunction "1_7") (pintype "passive"))
      (node (ref "T8") (pin "G") (pinfunction "G_G") (pintype "passive"))
    )
    (net (code "90") (name "Net-(RN8B-1)") (class "Default")
      (node (ref "JP1") (pin "7") (pinfunction "7_7") (pintype "passive"))
      (node (ref "RN8") (pin "3") (pinfunction "1_3") (pintype "passive"))
    )
    (net (code "91") (name "Net-(RN8C-2)") (class "Default")
      (node (ref "JP1") (pin "8") (pinfunction "8_8") (pintype "passive"))
      (node (ref "RN8") (pin "6") (pinfunction "2_6") (pintype "passive"))
    )
    (net (code "92") (name "Net-(RN8D-1)") (class "Default")
      (node (ref "JP1") (pin "9") (pinfunction "9_9") (pintype "passive"))
      (node (ref "RN8") (pin "7") (pinfunction "1_7") (pintype "passive"))
    )
    (net (code "93") (name "Net-(RN9B-1)") (class "Default")
      (node (ref "Q10") (pin "C") (pinfunction "C_C") (pintype "passive"))
      (node (ref "RN9") (pin "3") (pinfunction "1_3") (pintype "passive"))
      (node (ref "X2") (pin "2") (pinfunction "SK_2") (pintype "passive"))
    )
    (net (code "94") (name "Net-(RN9C-1)") (class "Default")
      (node (ref "Q11") (pin "C") (pinfunction "C_C") (pintype "passive"))
      (node (ref "RN9") (pin "5") (pinfunction "1_5") (pintype "passive"))
      (node (ref "X2") (pin "3") (pinfunction "SK_3") (pintype "passive"))
    )
    (net (code "95") (name "Net-(RN9D-1)") (class "Default")
      (node (ref "Q12") (pin "C") (pinfunction "C_C") (pintype "passive"))
      (node (ref "RN9") (pin "7") (pinfunction "1_7") (pintype "passive"))
      (node (ref "X2") (pin "4") (pinfunction "SK_4") (pintype "passive"))
    )
    (net (code "96") (name "Net-(RN10B-1)") (class "Default")
      (node (ref "C10") (pin "1") (pinfunction "1_1") (pintype "passive"))
      (node (ref "RN10") (pin "3") (pinfunction "1_3") (pintype "passive"))
      (node (ref "RN11") (pin "3") (pinfunction "1_3") (pintype "passive"))
      (node (ref "T10") (pin "G") (pinfunction "G_G") (pintype "passive"))
    )
    (net (code "97") (name "Net-(RN10B-2)") (class "Default")
      (node (ref "R10") (pin "2") (pinfunction "2_2") (pintype "passive"))
      (node (ref "R11") (pin "2") (pinfunction "2_2") (pintype "passive"))
      (node (ref "R12") (pin "2") (pinfunction "2_2") (pintype "passive"))
      (node (ref "R13") (pin "2") (pinfunction "2_2") (pintype "passive"))
      (node (ref "R14") (pin "2") (pinfunction "2_2") (pintype "passive"))
      (node (ref "R15") (pin "2") (pinfunction "2_2") (pintype "passive"))
      (node (ref "R16") (pin "2") (pinfunction "2_2") (pintype "passive"))
      (node (ref "R9") (pin "2") (pinfunction "2_2") (pintype "passive"))
      (node (ref "RN10") (pin "2") (pinfunction "2_2") (pintype "passive"))
      (node (ref "RN10") (pin "4") (pinfunction "2_4") (pintype "passive"))
      (node (ref "RN10") (pin "6") (pinfunction "2_6") (pintype "passive"))
      (node (ref "RN10") (pin "8") (pinfunction "2_8") (pintype "passive"))
      (node (ref "RN14") (pin "2") (pinfunction "2_2") (pintype "passive"))
      (node (ref "RN14") (pin "4") (pinfunction "2_4") (pintype "passive"))
      (node (ref "RN14") (pin "6") (pinfunction "2_6") (pintype "passive"))
      (node (ref "RN14") (pin "8") (pinfunction "2_8") (pintype "passive"))
      (node (ref "T10") (pin "A") (pinfunction "A_A") (pintype "passive"))
      (node (ref "T11") (pin "A") (pinfunction "A_A") (pintype "passive"))
      (node (ref "T12") (pin "A") (pinfunction "A_A") (pintype "passive"))
      (node (ref "T13") (pin "A") (pinfunction "A_A") (pintype "passive"))
      (node (ref "T14") (pin "A") (pinfunction "A_A") (pintype "passive"))
      (node (ref "T15") (pin "A") (pinfunction "A_A") (pintype "passive"))
      (node (ref "T16") (pin "A") (pinfunction "A_A") (pintype "passive"))
      (node (ref "T9") (pin "A") (pinfunction "A_A") (pintype "passive"))
      (node (ref "X2") (pin "5") (pinfunction "SK_5") (pintype "passive"))
    )
    (net (code "98") (name "Net-(RN10C-1)") (class "Default")
      (node (ref "C11") (pin "1") (pinfunction "1_1") (pintype "passive"))
      (node (ref "RN10") (pin "5") (pinfunction "1_5") (pintype "passive"))
      (node (ref "RN11") (pin "5") (pinfunction "1_5") (pintype "passive"))
      (node (ref "T11") (pin "G") (pinfunction "G_G") (pintype "passive"))
    )
    (net (code "99") (name "Net-(RN10D-1)") (class "Default")
      (node (ref "C12") (pin "1") (pinfunction "1_1") (pintype "passive"))
      (node (ref "RN10") (pin "7") (pinfunction "1_7") (pintype "passive"))
      (node (ref "RN11") (pin "7") (pinfunction "1_7") (pintype "passive"))
      (node (ref "T12") (pin "G") (pinfunction "G_G") (pintype "passive"))
    )
    (net (code "100") (name "Net-(RN12B-1)") (class "Default")
      (node (ref "JP1") (pin "11") (pinfunction "11_11") (pintype "passive"))
      (node (ref "RN12") (pin "3") (pinfunction "1_3") (pintype "passive"))
    )
    (net (code "101") (name "Net-(RN12C-2)") (class "Default")
      (node (ref "JP1") (pin "12") (pinfunction "12_12") (pintype "passive"))
      (node (ref "RN12") (pin "6") (pinfunction "2_6") (pintype "passive"))
    )
    (net (code "102") (name "Net-(RN12D-1)") (class "Default")
      (node (ref "JP1") (pin "13") (pinfunction "13_13") (pintype "passive"))
      (node (ref "RN12") (pin "7") (pinfunction "1_7") (pintype "passive"))
    )
    (net (code "103") (name "Net-(RN13B-1)") (class "Default")
      (node (ref "Q14") (pin "C") (pinfunction "C_C") (pintype "passive"))
      (node (ref "RN13") (pin "3") (pinfunction "1_3") (pintype "passive"))
      (node (ref "X2") (pin "7") (pinfunction "SK_7") (pintype "passive"))
    )
    (net (code "104") (name "Net-(RN13C-1)") (class "Default")
      (node (ref "Q15") (pin "C") (pinfunction "C_C") (pintype "passive"))
      (node (ref "RN13") (pin "5") (pinfunction "1_5") (pintype "passive"))
      (node (ref "X2") (pin "8") (pinfunction "SK_8") (pintype "passive"))
    )
    (net (code "105") (name "Net-(RN13D-1)") (class "Default")
      (node (ref "Q16") (pin "C") (pinfunction "C_C") (pintype "passive"))
      (node (ref "RN13") (pin "7") (pinfunction "1_7") (pintype "passive"))
      (node (ref "X2") (pin "9") (pinfunction "SK_9") (pintype "passive"))
    )
    (net (code "106") (name "Net-(RN14B-1)") (class "Default")
      (node (ref "C14") (pin "1") (pinfunction "1_1") (pintype "passive"))
      (node (ref "RN14") (pin "3") (pinfunction "1_3") (pintype "passive"))
      (node (ref "RN15") (pin "3") (pinfunction "1_3") (pintype "passive"))
      (node (ref "T14") (pin "G") (pinfunction "G_G") (pintype "passive"))
    )
    (net (code "107") (name "Net-(RN14C-1)") (class "Default")
      (node (ref "C15") (pin "1") (pinfunction "1_1") (pintype "passive"))
      (node (ref "RN14") (pin "5") (pinfunction "1_5") (pintype "passive"))
      (node (ref "RN15") (pin "5") (pinfunction "1_5") (pintype "passive"))
      (node (ref "T15") (pin "G") (pinfunction "G_G") (pintype "passive"))
    )
    (net (code "108") (name "Net-(RN14D-1)") (class "Default")
      (node (ref "C16") (pin "1") (pinfunction "1_1") (pintype "passive"))
      (node (ref "RN14") (pin "7") (pinfunction "1_7") (pintype "passive"))
      (node (ref "RN15") (pin "7") (pinfunction "1_7") (pintype "passive"))
      (node (ref "T16") (pin "G") (pinfunction "G_G") (pintype "passive"))
    )
    (net (code "109") (name "Net-(RN16B-1)") (class "Default")
      (node (ref "JP1") (pin "15") (pinfunction "15_15") (pintype "passive"))
      (node (ref "RN16") (pin "3") (pinfunction "1_3") (pintype "passive"))
    )
    (net (code "110") (name "Net-(RN16C-2)") (class "Default")
      (node (ref "JP1") (pin "16") (pinfunction "16_16") (pintype "passive"))
      (node (ref "RN16") (pin "6") (pinfunction "2_6") (pintype "passive"))
    )
    (net (code "111") (name "Net-(RN16D-1)") (class "Default")
      (node (ref "JP1") (pin "17") (pinfunction "17_17") (pintype "passive"))
      (node (ref "RN16") (pin "7") (pinfunction "1_7") (pintype "passive"))
    )
    (net (code "112") (name "Net-(X1A-SK)") (class "Default")
      (node (ref "Q1") (pin "C") (pinfunction "C_C") (pintype "passive"))
      (node (ref "RN4") (pin "1") (pinfunction "1_1") (pintype "passive"))
      (node (ref "X1") (pin "1") (pinfunction "SK_1") (pintype "passive"))
    )
    (net (code "113") (name "Net-(X1F-SK)") (class "Default")
      (node (ref "Q5") (pin "C") (pinfunction "C_C") (pintype "passive"))
      (node (ref "RN5") (pin "1") (pinfunction "1_1") (pintype "passive"))
      (node (ref "X1") (pin "6") (pinfunction "SK_6") (pintype "passive"))
    )
    (net (code "114") (name "Net-(X2A-SK)") (class "Default")
      (node (ref "Q9") (pin "C") (pinfunction "C_C") (pintype "passive"))
      (node (ref "RN9") (pin "1") (pinfunction "1_1") (pintype "passive"))
      (node (ref "X2") (pin "1") (pinfunction "SK_1") (pintype "passive"))
    )
    (net (code "115") (name "Net-(X2F-SK)") (class "Default")
      (node (ref "Q13") (pin "C") (pinfunction "C_C") (pintype "passive"))
      (node (ref "RN13") (pin "1") (pinfunction "1_1") (pintype "passive"))
      (node (ref "X2") (pin "6") (pinfunction "SK_6") (pintype "passive"))
    )
    (net (code "116") (name "VCC") (class "Default")
      (node (ref "JP1") (pin "1") (pinfunction "1_1") (pintype "passive"))
    )
    (net (code "117") (name "unconnected-(H1-MOUNT-PadB3,6)") (class "Default")
      (node (ref "H1") (pin "B3,6") (pinfunction "MOUNT_B3,6") (pintype "passive"))
    )
  )
)
